# Sound_Light_IC_evaluation_board_ask.net
KiCad netlist of a schematic drawn in Altium Designer
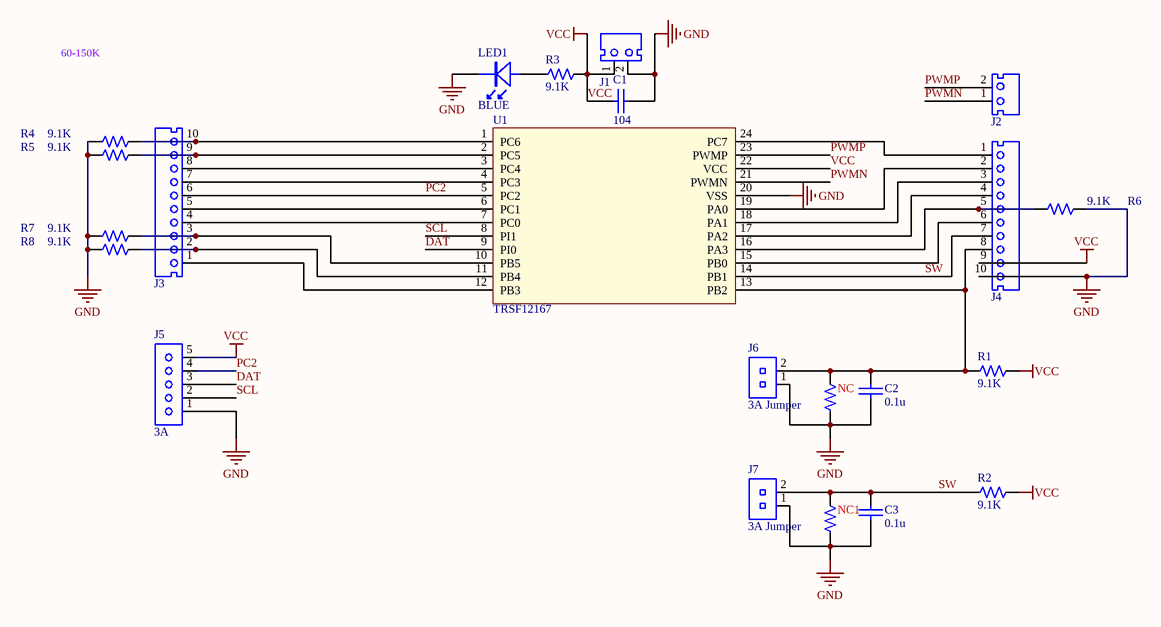
[diagram p0: Sound&Light IC evaluation board ask.SchDoc]

(export (version "E")
  (design (tool "Eeschema 10.0.6"))
  (components
    (comp (ref "C1")
      (value "104")
      (footprint "CAPC0603-RW")
      (description "CAP X7R .01UF 50V +-5% 0603 WALSIN L")
      (fields
        (field (name "MFG") "WALSIN")
        (field (name "TOLERANCE") "5%")
        (field (name "CREATE_NAME") "Nathan")
      )
      (libsource (lib "P-Capacitors") (part "CAP0603 0.01uF 50V 5%_X7R_WALSIN"))
    )
    (comp (ref "C2")
      (value "0.1u")
      (footprint "CAPC0603-RW")
      (description "CAP X7R .01UF 50V +-5% 0603 WALSIN L")
      (fields
        (field (name "MFG") "WALSIN")
        (field (name "TOLERANCE") "5%")
        (field (name "CREATE_NAME") "Nathan")
      )
      (libsource (lib "P-Capacitors") (part "CAP0603 0.01uF 50V 5%_X7R_WALSIN"))
    )
    (comp (ref "C3")
      (value "0.1u")
      (footprint "CAPC0603-RW")
      (description "CAP X7R .01UF 50V +-5% 0603 WALSIN L")
      (fields
        (field (name "MFG") "WALSIN")
        (field (name "TOLERANCE") "5%")
        (field (name "CREATE_NAME") "Nathan")
      )
      (libsource (lib "P-Capacitors") (part "CAP0603 0.01uF 50V 5%_X7R_WALSIN"))
    )
    (comp (ref "J1")
      (value "T690300125300")
      (footprint "CONN 2P PH=2.5mm HAA250A-2 WHITE")
      (description "CONNECTOR HA2.5 2PIN BLACK K")
      (fields
        (field (name "MFG") "金瑞康")
        (field (name "MFG PART") "HAA250A-2 BLACK")
        (field (name "CREATE_NAME") "Nathan")
      )
      (libsource (lib "C-Connector") (part "CONN 2P PH=2.5mm HAA250A-2 BLACK"))
    )
    (comp (ref "J2")
      (value "T690300125300")
      (footprint "CONN 2P PH=2.5mm HAA250A-2 WHITE")
      (description "CONNECTOR HA2.5 2PIN BLACK K")
      (fields
        (field (name "MFG") "金瑞康")
        (field (name "MFG PART") "HAA250A-2 BLACK")
        (field (name "CREATE_NAME") "Nathan")
      )
      (libsource (lib "C-Connector") (part "CONN 2P PH=2.5mm HAA250A-2 BLACK"))
    )
    (comp (ref "J3")
      (value "T690300105400")
      (footprint "CONN 10P PH=2.5mm ST CI2210P1VK0-NH")
      (description "WTB CONN. 2.5MM 10PIN CI2210P1VK0-NH CV G")
      (fields
        (field (name "MFG") "CVILUX")
        (field (name "MFG PART") "CI2210P1VK0-NH")
        (field (name "CREATE_NAME") "Nathan")
      )
      (libsource (lib "C-Connector") (part "CONN 10P PH=2.5mm ST CI2210P1VK0-NH"))
    )
    (comp (ref "J4")
      (value "T690300105400")
      (footprint "CONN 10P PH=2.5mm ST CI2210P1VK0-NH")
      (description "WTB CONN. 2.5MM 10PIN CI2210P1VK0-NH CV G")
      (fields
        (field (name "MFG") "CVILUX")
        (field (name "MFG PART") "CI2210P1VK0-NH")
        (field (name "CREATE_NAME") "Nathan")
      )
      (libsource (lib "C-Connector") (part "CONN 10P PH=2.5mm ST CI2210P1VK0-NH"))
    )
    (comp (ref "J5")
      (value "CCP254260-0105")
      (footprint "HEAD 5P PH=2.54mm 180")
      (description "HEAD PIN 5P P2.54xH11.5MM")
      (fields (field (name "CURRENT") "3A"))
      (libsource (lib "C-Connector") (part "HEAD 5P PH=2.54mm 180"))
    )
    (comp (ref "J6")
      (value "CCH254020-0102")
      (footprint "HOUSING 2P PH=2.54mm Jumper")
      (description "HOUSING SIL Jumper 2P 90059-1007 Molex")
      (fields (field (name "CURRENT") "3A Jumper"))
      (libsource (lib "C-Connector") (part "HOUSING 2P PH=2.54mm Jumper"))
    )
    (comp (ref "J7")
      (value "CCH254020-0102")
      (footprint "HOUSING 2P PH=2.54mm Jumper")
      (description "HOUSING SIL Jumper 2P 90059-1007 Molex")
      (fields (field (name "CURRENT") "3A Jumper"))
      (libsource (lib "C-Connector") (part "HOUSING 2P PH=2.54mm Jumper"))
    )
    (comp (ref "LED1")
      (value "T575011480204")
      (footprint "LED0603_BLUE")
      (description "LED 465 0603 LTST-C193TBK LITEON ( L")
      (fields
        (field (name "MFG PART") "LTST-C193TBKT-5A")
        (field (name "MFG") "LITEON (光寶)")
        (field (name "COLOR") "BLUE")
        (field (name "CREATE_NAME") "Nathan")
      )
      (libsource (lib "K-LED-FUSE") (part "LED0603B_LTST-C193TBKT-5A"))
    )
    (comp (ref "NC")
      (value "T502294202399")
      (footprint "0603-RW")
      (description "CHIP 29.4K OHM 100PPM +-1% 0603 WALS L")
      (fields (field (name "POWER") "1/10W") (field (name "MFG") "WALSIN") (field (name "CREATE_NAME") "Tom"))
      (libsource (lib "Q-Resistors") (part "RES0603 1/10W +-0.1% 29.4K OHM 100PPM"))
    )
    (comp (ref "NC1")
      (value "T502294202399")
      (footprint "0603-RW")
      (description "CHIP 29.4K OHM 100PPM +-1% 0603 WALS L")
      (fields (field (name "POWER") "1/10W") (field (name "MFG") "WALSIN") (field (name "CREATE_NAME") "Tom"))
      (libsource (lib "Q-Resistors") (part "RES0603 1/10W +-0.1% 29.4K OHM 100PPM"))
    )
    (comp (ref "R1")
      (value "9.1K")
      (footprint "0603-RW")
      (description "CHIP 29.4K OHM 100PPM +-1% 0603 WALS L")
      (fields (field (name "POWER") "1/10W") (field (name "MFG") "WALSIN") (field (name "CREATE_NAME") "Tom"))
      (libsource (lib "Q-Resistors") (part "RES0603 1/10W +-0.1% 29.4K OHM 100PPM"))
    )
    (comp (ref "R2")
      (value "9.1K")
      (footprint "0603-RW")
      (description "CHIP 29.4K OHM 100PPM +-1% 0603 WALS L")
      (fields (field (name "POWER") "1/10W") (field (name "MFG") "WALSIN") (field (name "CREATE_NAME") "Tom"))
      (libsource (lib "Q-Resistors") (part "RES0603 1/10W +-0.1% 29.4K OHM 100PPM"))
    )
    (comp (ref "R3")
      (value "9.1K")
      (footprint "0603-RW")
      (description "CHIP 29.4K OHM 100PPM +-1% 0603 WALS L")
      (fields (field (name "POWER") "1/10W") (field (name "MFG") "WALSIN") (field (name "CREATE_NAME") "Tom"))
      (libsource (lib "Q-Resistors") (part "RES0603 1/10W +-0.1% 29.4K OHM 100PPM"))
    )
    (comp (ref "R4")
      (value "9.1K")
      (footprint "0603-RW")
      (description "CHIP 29.4K OHM 100PPM +-1% 0603 WALS L")
      (fields (field (name "POWER") "1/10W") (field (name "MFG") "WALSIN") (field (name "CREATE_NAME") "Tom"))
      (libsource (lib "Q-Resistors") (part "RES0603 1/10W +-0.1% 29.4K OHM 100PPM"))
    )
    (comp (ref "R5")
      (value "9.1K")
      (footprint "0603-RW")
      (description "CHIP 29.4K OHM 100PPM +-1% 0603 WALS L")
      (fields (field (name "POWER") "1/10W") (field (name "MFG") "WALSIN") (field (name "CREATE_NAME") "Tom"))
      (libsource (lib "Q-Resistors") (part "RES0603 1/10W +-0.1% 29.4K OHM 100PPM"))
    )
    (comp (ref "R6")
      (value "9.1K")
      (footprint "0603-RW")
      (description "CHIP 29.4K OHM 100PPM +-1% 0603 WALS L")
      (fields (field (name "POWER") "1/10W") (field (name "MFG") "WALSIN") (field (name "CREATE_NAME") "Tom"))
      (libsource (lib "Q-Resistors") (part "RES0603 1/10W +-0.1% 29.4K OHM 100PPM"))
    )
    (comp (ref "R7")
      (value "9.1K")
      (footprint "0603-RW")
      (description "CHIP 29.4K OHM 100PPM +-1% 0603 WALS L")
      (fields (field (name "POWER") "1/10W") (field (name "MFG") "WALSIN") (field (name "CREATE_NAME") "Tom"))
      (libsource (lib "Q-Resistors") (part "RES0603 1/10W +-0.1% 29.4K OHM 100PPM"))
    )
    (comp (ref "R8")
      (value "9.1K")
      (footprint "0603-RW")
      (description "CHIP 29.4K OHM 100PPM +-1% 0603 WALS L")
      (fields (field (name "POWER") "1/10W") (field (name "MFG") "WALSIN") (field (name "CREATE_NAME") "Tom"))
      (libsource (lib "Q-Resistors") (part "RES0603 1/10W +-0.1% 29.4K OHM 100PPM"))
    )
    (comp (ref "U1")
      (value "BS86C08C 24SSOP")
      (footprint "SSOP24(150mil)")
      (description "BS86C08C_24SSOP")
      (fields
        (field (name "MFG") "HOLTEK")
        (field (name "MFG PART") "TRSF12167")
        (field (name "CREATE_NAME") "Nathan")
      )
      (libsource (lib "R-Semiconductors") (part "BS86C08C 24SSOP"))
    )
  )
  (nets
    (net (code "1") (name "/DAT") (class "Default")
      (node (ref "J5") (pin "3") (pinfunction "3_3") (pintype "passive"))
      (node (ref "U1") (pin "9") (pinfunction "PI0_9") (pintype "passive"))
    )
    (net (code "2") (name "/PC2") (class "Default")
      (node (ref "J3") (pin "6") (pinfunction "6_6") (pintype "passive"))
      (node (ref "J5") (pin "4") (pinfunction "4_4") (pintype "passive"))
      (node (ref "U1") (pin "5") (pinfunction "PC2_5") (pintype "passive"))
    )
    (net (code "3") (name "/PWMN") (class "Default")
      (node (ref "J2") (pin "1") (pinfunction "1_1") (pintype "passive"))
      (node (ref "U1") (pin "21") (pinfunction "PWMN_21") (pintype "passive"))
    )
    (net (code "4") (name "/PWMP") (class "Default")
      (node (ref "J2") (pin "2") (pinfunction "2_2") (pintype "passive"))
      (node (ref "U1") (pin "23") (pinfunction "PWMP_23") (pintype "passive"))
    )
    (net (code "5") (name "/SCL") (class "Default")
      (node (ref "J5") (pin "2") (pinfunction "2_2") (pintype "passive"))
      (node (ref "U1") (pin "8") (pinfunction "PI1_8") (pintype "passive"))
    )
    (net (code "6") (name "/SW") (class "Default")
      (node (ref "C3") (pin "2") (pinfunction "2_2") (pintype "passive"))
      (node (ref "J4") (pin "7") (pinfunction "7_7") (pintype "passive"))
      (node (ref "J7") (pin "2") (pinfunction "2_2") (pintype "passive"))
      (node (ref "NC1") (pin "2") (pinfunction "2_2") (pintype "passive"))
      (node (ref "R2") (pin "1") (pinfunction "1_1") (pintype "passive"))
      (node (ref "U1") (pin "14") (pinfunction "PB1_14") (pintype "passive"))
    )
    (net (code "7") (name "GND") (class "Default")
      (node (ref "C1") (pin "1") (pinfunction "1_1") (pintype "passive"))
      (node (ref "C2") (pin "1") (pinfunction "1_1") (pintype "passive"))
      (node (ref "C3") (pin "1") (pinfunction "1_1") (pintype "passive"))
      (node (ref "J1") (pin "2") (pinfunction "2_2") (pintype "passive"))
      (node (ref "J4") (pin "10") (pinfunction "10_10") (pintype "passive"))
      (node (ref "J5") (pin "1") (pinfunction "1_1") (pintype "passive"))
      (node (ref "J6") (pin "1") (pinfunction "1_1") (pintype "passive"))
      (node (ref "J7") (pin "1") (pinfunction "1_1") (pintype "passive"))
      (node (ref "LED1") (pin "2") (pinfunction "K_2") (pintype "passive"))
      (node (ref "NC") (pin "1") (pinfunction "1_1") (pintype "passive"))
      (node (ref "NC1") (pin "1") (pinfunction "1_1") (pintype "passive"))
      (node (ref "R4") (pin "1") (pinfunction "1_1") (pintype "passive"))
      (node (ref "R5") (pin "1") (pinfunction "1_1") (pintype "passive"))
      (node (ref "R6") (pin "2") (pinfunction "2_2") (pintype "passive"))
      (node (ref "R7") (pin "1") (pinfunction "1_1") (pintype "passive"))
      (node (ref "R8") (pin "1") (pinfunction "1_1") (pintype "passive"))
      (node (ref "U1") (pin "20") (pinfunction "VSS_20") (pintype "passive"))
    )
    (net (code "8") (name "Net-(LED1-A)") (class "Default")
      (node (ref "LED1") (pin "1") (pinfunction "A_1") (pintype "passive"))
      (node (ref "R3") (pin "1") (pinfunction "1_1") (pintype "passive"))
    )
    (net (code "9") (name "Net-(U1-PA0)") (class "Default")
      (node (ref "J4") (pin "2") (pinfunction "2_2") (pintype "passive"))
      (node (ref "U1") (pin "19") (pinfunction "PA0_19") (pintype "passive"))
    )
    (net (code "10") (name "Net-(U1-PA1)") (class "Default")
      (node (ref "J4") (pin "3") (pinfunction "3_3") (pintype "passive"))
      (node (ref "U1") (pin "18") (pinfunction "PA1_18") (pintype "passive"))
    )
    (net (code "11") (name "Net-(U1-PA2)") (class "Default")
      (node (ref "J4") (pin "4") (pinfunction "4_4") (pintype "passive"))
      (node (ref "U1") (pin "17") (pinfunction "PA2_17") (pintype "passive"))
    )
    (net (code "12") (name "Net-(U1-PA3)") (class "Default")
      (node (ref "J4") (pin "5") (pinfunction "5_5") (pintype "passive"))
      (node (ref "R6") (pin "1") (pinfunction "1_1") (pintype "passive"))
      (node (ref "U1") (pin "16") (pinfunction "PA3_16") (pintype "passive"))
    )
    (net (code "13") (name "Net-(U1-PB0)") (class "Default")
      (node (ref "J4") (pin "6") (pinfunction "6_6") (pintype "passive"))
      (node (ref "U1") (pin "15") (pinfunction "PB0_15") (pintype "passive"))
    )
    (net (code "14") (name "Net-(U1-PB2)") (class "Default")
      (node (ref "C2") (pin "2") (pinfunction "2_2") (pintype "passive"))
      (node (ref "J4") (pin "8") (pinfunction "8_8") (pintype "passive"))
      (node (ref "J6") (pin "2") (pinfunction "2_2") (pintype "passive"))
      (node (ref "NC") (pin "2") (pinfunction "2_2") (pintype "passive"))
      (node (ref "R1") (pin "1") (pinfunction "1_1") (pintype "passive"))
      (node (ref "U1") (pin "13") (pinfunction "PB2_13") (pintype "passive"))
    )
    (net (code "15") (name "Net-(U1-PB3)") (class "Default")
      (node (ref "J3") (pin "1") (pinfunction "1_1") (pintype "passive"))
      (node (ref "U1") (pin "12") (pinfunction "PB3_12") (pintype "passive"))
    )
    (net (code "16") (name "Net-(U1-PB4)") (class "Default")
      (node (ref "J3") (pin "2") (pinfunction "2_2") (pintype "passive"))
      (node (ref "R8") (pin "2") (pinfunction "2_2") (pintype "passive"))
      (node (ref "U1") (pin "11") (pinfunction "PB4_11") (pintype "passive"))
    )
    (net (code "17") (name "Net-(U1-PB5)") (class "Default")
      (node (ref "J3") (pin "3") (pinfunction "3_3") (pintype "passive"))
      (node (ref "R7") (pin "2") (pinfunction "2_2") (pintype "passive"))
      (node (ref "U1") (pin "10") (pinfunction "PB5_10") (pintype "passive"))
    )
    (net (code "18") (name "Net-(U1-PC0)") (class "Default")
      (node (ref "J3") (pin "4") (pinfunction "4_4") (pintype "passive"))
      (node (ref "U1") (pin "7") (pinfunction "PC0_7") (pintype "passive"))
    )
    (net (code "19") (name "Net-(U1-PC1)") (class "Default")
      (node (ref "J3") (pin "5") (pinfunction "5_5") (pintype "passive"))
      (node (ref "U1") (pin "6") (pinfunction "PC1_6") (pintype "passive"))
    )
    (net (code "20") (name "Net-(U1-PC3)") (class "Default")
      (node (ref "J3") (pin "7") (pinfunction "7_7") (pintype "passive"))
      (node (ref "U1") (pin "4") (pinfunction "PC3_4") (pintype "passive"))
    )
    (net (code "21") (name "Net-(U1-PC4)") (class "Default")
      (node (ref "J3") (pin "8") (pinfunction "8_8") (pintype "passive"))
      (node (ref "U1") (pin "3") (pinfunction "PC4_3") (pintype "passive"))
    )
    (net (code "22") (name "Net-(U1-PC5)") (class "Default")
      (node (ref "J3") (pin "9") (pinfunction "9_9") (pintype "passive"))
      (node (ref "R5") (pin "2") (pinfunction "2_2") (pintype "passive"))
      (node (ref "U1") (pin "2") (pinfunction "PC5_2") (pintype "passive"))
    )
    (net (code "23") (name "Net-(U1-PC6)") (class "Default")
      (node (ref "J3") (pin "10") (pinfunction "10_10") (pintype "passive"))
      (node (ref "R4") (pin "2") (pinfunction "2_2") (pintype "passive"))
      (node (ref "U1") (pin "1") (pinfunction "PC6_1") (pintype "passive"))
    )
    (net (code "24") (name "Net-(U1-PC7)") (class "Default")
      (node (ref "J4") (pin "1") (pinfunction "1_1") (pintype "passive"))
      (node (ref "U1") (pin "24") (pinfunction "PC7_24") (pintype "passive"))
    )
    (net (code "25") (name "VCC") (class "Default")
      (node (ref "C1") (pin "2") (pinfunction "2_2") (pintype "passive"))
      (node (ref "J1") (pin "1") (pinfunction "1_1") (pintype "passive"))
      (node (ref "J4") (pin "9") (pinfunction "9_9") (pintype "passive"))
      (node (ref "J5") (pin "5") (pinfunction "5_5") (pintype "passive"))
      (node (ref "R1") (pin "2") (pinfunction "2_2") (pintype "passive"))
      (node (ref "R2") (pin "2") (pinfunction "2_2") (pintype "passive"))
      (node (ref "R3") (pin "2") (pinfunction "2_2") (pintype "passive"))
      (node (ref "U1") (pin "22") (pinfunction "VCC_22") (pintype "passive"))
    )
  )
)
